# input3.net
KiCad netlist of a schematic drawn in Altium Designer
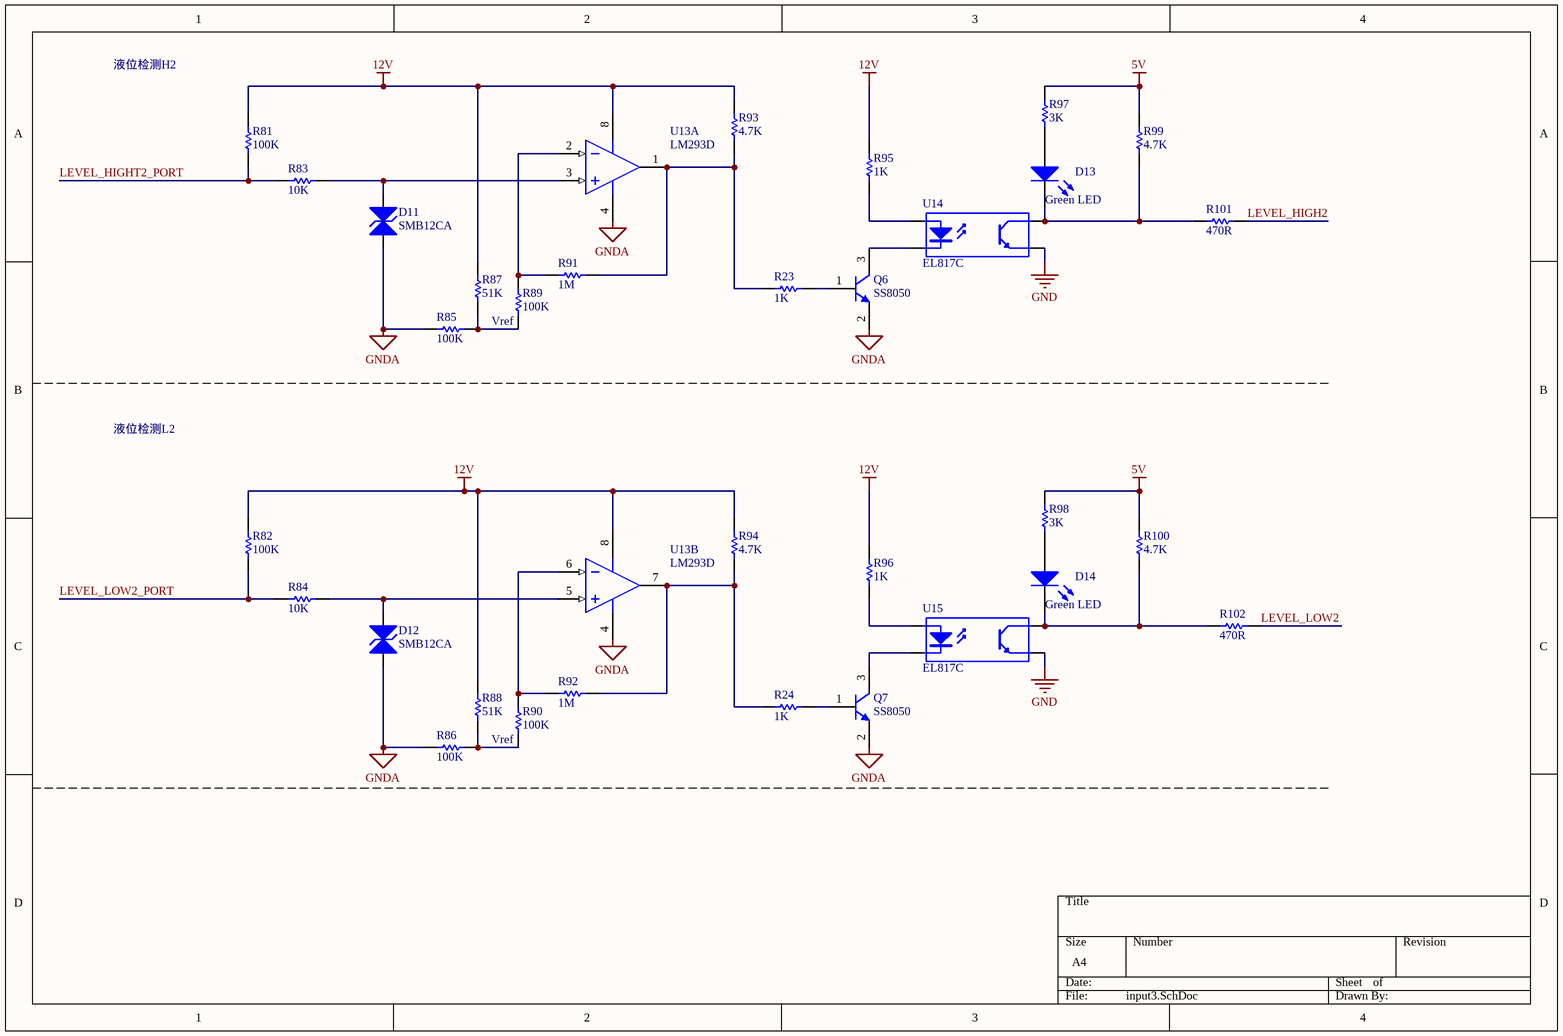
[diagram p0: input3.SchDoc]

(export (version "E")
  (design (tool "Eeschema 10.0.6"))
  (components
    (comp (ref "D11")
      (value "SMB12CA")
      (footprint "SMB")
      (description "Bi-dir TVS Diode")
      (fields (field (name "PUBLISHER") "Altium Limited"))
      (libsource (lib "UserLib") (part "Bi-dir TVS Diode"))
    )
    (comp (ref "D12")
      (value "SMB12CA")
      (footprint "SMB")
      (description "Bi-dir TVS Diode")
      (fields (field (name "PUBLISHER") "Altium Limited"))
      (libsource (lib "UserLib") (part "Bi-dir TVS Diode"))
    )
    (comp (ref "D13")
      (value "Green LED")
      (footprint "LED254A")
      (description "Green LED ,SIP, Dia =3mm")
      (fields (field (name "PUBLISHER") "Altium Limited"))
      (libsource (lib "Miscellaneous Devices") (part "LED1"))
    )
    (comp (ref "D14")
      (value "Green LED")
      (footprint "LED254A")
      (description "Green LED ,SIP, Dia =3mm")
      (fields (field (name "PUBLISHER") "Altium Limited"))
      (libsource (lib "Miscellaneous Devices") (part "LED1"))
    )
    (comp (ref "Q6")
      (value "SS8050")
      (footprint "SOT-23_N")
      (description "NPN BISS Transistor")
      (fields (field (name "PUBLISHER") "Altium Limited"))
      (libsource (lib "Philips Discrete BJT - Low Power") (part "PMMT491A"))
    )
    (comp (ref "Q7")
      (value "SS8050")
      (footprint "SOT-23_N")
      (description "NPN BISS Transistor")
      (fields (field (name "PUBLISHER") "Altium Limited"))
      (libsource (lib "Philips Discrete BJT - Low Power") (part "PMMT491A"))
    )
    (comp (ref "R23")
      (value "1K")
      (footprint "RESC2012M")
      (description "Resistor")
      (fields (field (name "PUBLISHER") "Altium Limited"))
      (libsource (lib "Miscellaneous Devices") (part "Res1"))
    )
    (comp (ref "R24")
      (value "1K")
      (footprint "RESC2012M")
      (description "Resistor")
      (fields (field (name "PUBLISHER") "Altium Limited"))
      (libsource (lib "Miscellaneous Devices") (part "Res1"))
    )
    (comp (ref "R81")
      (value "100K")
      (footprint "RESC2012M")
      (description "Resistor")
      (fields (field (name "PUBLISHER") "Altium Limited"))
      (libsource (lib "Miscellaneous Devices") (part "Res1"))
    )
    (comp (ref "R82")
      (value "100K")
      (footprint "RESC2012M")
      (description "Resistor")
      (fields (field (name "PUBLISHER") "Altium Limited"))
      (libsource (lib "Miscellaneous Devices") (part "Res1"))
    )
    (comp (ref "R83")
      (value "10K")
      (footprint "RESC2012M")
      (description "Resistor")
      (fields (field (name "PUBLISHER") "Altium Limited"))
      (libsource (lib "Miscellaneous Devices") (part "Res1"))
    )
    (comp (ref "R84")
      (value "10K")
      (footprint "RESC2012M")
      (description "Resistor")
      (fields (field (name "PUBLISHER") "Altium Limited"))
      (libsource (lib "Miscellaneous Devices") (part "Res1"))
    )
    (comp (ref "R85")
      (value "100K")
      (footprint "RESC2012M")
      (description "Resistor")
      (fields (field (name "PUBLISHER") "Altium Limited"))
      (libsource (lib "Miscellaneous Devices") (part "Res1"))
    )
    (comp (ref "R86")
      (value "100K")
      (footprint "RESC2012M")
      (description "Resistor")
      (fields (field (name "PUBLISHER") "Altium Limited"))
      (libsource (lib "Miscellaneous Devices") (part "Res1"))
    )
    (comp (ref "R87")
      (value "51K")
      (footprint "RESC2012M")
      (description "Resistor")
      (fields (field (name "PUBLISHER") "Altium Limited"))
      (libsource (lib "Miscellaneous Devices") (part "Res1"))
    )
    (comp (ref "R88")
      (value "51K")
      (footprint "RESC2012M")
      (description "Resistor")
      (fields (field (name "PUBLISHER") "Altium Limited"))
      (libsource (lib "Miscellaneous Devices") (part "Res1"))
    )
    (comp (ref "R89")
      (value "100K")
      (footprint "RESC2012M")
      (description "Resistor")
      (fields (field (name "PUBLISHER") "Altium Limited"))
      (libsource (lib "Miscellaneous Devices") (part "Res1"))
    )
    (comp (ref "R90")
      (value "100K")
      (footprint "RESC2012M")
      (description "Resistor")
      (fields (field (name "PUBLISHER") "Altium Limited"))
      (libsource (lib "Miscellaneous Devices") (part "Res1"))
    )
    (comp (ref "R91")
      (value "1M")
      (footprint "RESC2012M")
      (description "Resistor")
      (fields (field (name "PUBLISHER") "Altium Limited"))
      (libsource (lib "Miscellaneous Devices") (part "Res1"))
    )
    (comp (ref "R92")
      (value "1M")
      (footprint "RESC2012M")
      (description "Resistor")
      (fields (field (name "PUBLISHER") "Altium Limited"))
      (libsource (lib "Miscellaneous Devices") (part "Res1"))
    )
    (comp (ref "R93")
      (value "4.7K")
      (footprint "RESC2012M")
      (description "Resistor")
      (fields (field (name "PUBLISHER") "Altium Limited"))
      (libsource (lib "Miscellaneous Devices") (part "Res1"))
    )
    (comp (ref "R94")
      (value "4.7K")
      (footprint "RESC2012M")
      (description "Resistor")
      (fields (field (name "PUBLISHER") "Altium Limited"))
      (libsource (lib "Miscellaneous Devices") (part "Res1"))
    )
    (comp (ref "R95")
      (value "1K")
      (footprint "RESC2012M")
      (description "Resistor")
      (fields (field (name "PUBLISHER") "Altium Limited"))
      (libsource (lib "Miscellaneous Devices") (part "Res1"))
    )
    (comp (ref "R96")
      (value "1K")
      (footprint "RESC2012M")
      (description "Resistor")
      (fields (field (name "PUBLISHER") "Altium Limited"))
      (libsource (lib "Miscellaneous Devices") (part "Res1"))
    )
    (comp (ref "R97")
      (value "3K")
      (footprint "RESC2012M")
      (description "Resistor")
      (fields (field (name "PUBLISHER") "Altium Limited"))
      (libsource (lib "Miscellaneous Devices") (part "Res1"))
    )
    (comp (ref "R98")
      (value "3K")
      (footprint "RESC2012M")
      (description "Resistor")
      (fields (field (name "PUBLISHER") "Altium Limited"))
      (libsource (lib "Miscellaneous Devices") (part "Res1"))
    )
    (comp (ref "R99")
      (value "4.7K")
      (footprint "RESC2012M")
      (description "Resistor")
      (fields (field (name "PUBLISHER") "Altium Limited"))
      (libsource (lib "Miscellaneous Devices") (part "Res1"))
    )
    (comp (ref "R100")
      (value "4.7K")
      (footprint "RESC2012M")
      (description "Resistor")
      (fields (field (name "PUBLISHER") "Altium Limited"))
      (libsource (lib "Miscellaneous Devices") (part "Res1"))
    )
    (comp (ref "R101")
      (value "470R")
      (footprint "RESC2012M")
      (description "Resistor")
      (fields (field (name "PUBLISHER") "Altium Limited"))
      (libsource (lib "Miscellaneous Devices") (part "Res1"))
    )
    (comp (ref "R102")
      (value "470R")
      (footprint "RESC2012M")
      (description "Resistor")
      (fields (field (name "PUBLISHER") "Altium Limited"))
      (libsource (lib "Miscellaneous Devices") (part "Res1"))
    )
    (comp (ref "U13")
      (value "LM293D")
      (footprint "SO8_N")
      (description "Low-Power Dual Voltage Comparator")
      (fields (field (name "PUBLISHER") "Altium Limited"))
      (libsource (lib "ST Analog Comparator") (part "LM393AD"))
    )
    (comp (ref "U14")
      (value "EL817C")
      (footprint "SO-4LA")
      (description "4-Pin Phototransistor Optocoupler")
      (fields (field (name "PUBLISHER") "Altium Limited"))
      (libsource (lib "Miscellaneous Devices") (part "Optoisolator1"))
    )
    (comp (ref "U15")
      (value "EL817C")
      (footprint "SO-4LA")
      (description "4-Pin Phototransistor Optocoupler")
      (fields (field (name "PUBLISHER") "Altium Limited"))
      (libsource (lib "Miscellaneous Devices") (part "Optoisolator1"))
    )
  )
  (nets
    (net (code "1") (name "/LEVEL_HIGH2") (class "Default")
      (node (ref "R101") (pin "2") (pinfunction "2_2") (pintype "passive"))
    )
    (net (code "2") (name "/LEVEL_HIGHT2_PORT") (class "Default")
      (node (ref "R81") (pin "1") (pinfunction "1_1") (pintype "passive"))
      (node (ref "R83") (pin "2") (pinfunction "2_2") (pintype "passive"))
    )
    (net (code "3") (name "/LEVEL_LOW2") (class "Default")
      (node (ref "R102") (pin "2") (pinfunction "2_2") (pintype "passive"))
    )
    (net (code "4") (name "/LEVEL_LOW2_PORT") (class "Default")
      (node (ref "R82") (pin "1") (pinfunction "1_1") (pintype "passive"))
      (node (ref "R84") (pin "2") (pinfunction "2_2") (pintype "passive"))
    )
    (net (code "5") (name "5V") (class "Default")
      (node (ref "R100") (pin "2") (pinfunction "2_2") (pintype "passive"))
      (node (ref "R97") (pin "1") (pinfunction "1_1") (pintype "passive"))
      (node (ref "R98") (pin "1") (pinfunction "1_1") (pintype "passive"))
      (node (ref "R99") (pin "2") (pinfunction "2_2") (pintype "passive"))
    )
    (net (code "6") (name "12V") (class "Default")
      (node (ref "R81") (pin "2") (pinfunction "2_2") (pintype "passive"))
      (node (ref "R82") (pin "2") (pinfunction "2_2") (pintype "passive"))
      (node (ref "R87") (pin "2") (pinfunction "2_2") (pintype "passive"))
      (node (ref "R88") (pin "2") (pinfunction "2_2") (pintype "passive"))
      (node (ref "R93") (pin "1") (pinfunction "1_1") (pintype "passive"))
      (node (ref "R94") (pin "2") (pinfunction "2_2") (pintype "passive"))
      (node (ref "R95") (pin "1") (pinfunction "1_1") (pintype "passive"))
      (node (ref "R96") (pin "1") (pinfunction "1_1") (pintype "passive"))
      (node (ref "U13") (pin "8") (pinfunction "V+_8") (pintype "power_in"))
    )
    (net (code "7") (name "GND") (class "Default")
      (node (ref "U14") (pin "3") (pinfunction "E_3") (pintype "passive"))
      (node (ref "U15") (pin "3") (pinfunction "E_3") (pintype "passive"))
    )
    (net (code "8") (name "GNDA") (class "Default")
      (node (ref "D11") (pin "1") (pinfunction "A_1") (pintype "passive"))
      (node (ref "D12") (pin "1") (pinfunction "A_1") (pintype "passive"))
      (node (ref "Q6") (pin "2") (pinfunction "E_2") (pintype "passive"))
      (node (ref "Q7") (pin "2") (pinfunction "E_2") (pintype "passive"))
      (node (ref "R85") (pin "1") (pinfunction "1_1") (pintype "passive"))
      (node (ref "R86") (pin "1") (pinfunction "1_1") (pintype "passive"))
      (node (ref "U13") (pin "4") (pinfunction "V-_4") (pintype "power_in"))
    )
    (net (code "9") (name "Net-(D11-K)") (class "Default")
      (node (ref "D11") (pin "2") (pinfunction "K_2") (pintype "passive"))
      (node (ref "R83") (pin "1") (pinfunction "1_1") (pintype "passive"))
      (node (ref "U13") (pin "3") (pinfunction "IN+_3") (pintype "input"))
    )
    (net (code "10") (name "Net-(D12-K)") (class "Default")
      (node (ref "D12") (pin "2") (pinfunction "K_2") (pintype "passive"))
      (node (ref "R84") (pin "1") (pinfunction "1_1") (pintype "passive"))
      (node (ref "U13") (pin "5") (pinfunction "IN+_5") (pintype "input"))
    )
    (net (code "11") (name "Net-(D13-A)") (class "Default")
      (node (ref "D13") (pin "1") (pinfunction "A_1") (pintype "passive"))
      (node (ref "R97") (pin "2") (pinfunction "2_2") (pintype "passive"))
    )
    (net (code "12") (name "Net-(D13-K)") (class "Default")
      (node (ref "D13") (pin "2") (pinfunction "K_2") (pintype "passive"))
      (node (ref "R101") (pin "1") (pinfunction "1_1") (pintype "passive"))
      (node (ref "R99") (pin "1") (pinfunction "1_1") (pintype "passive"))
      (node (ref "U14") (pin "4") (pinfunction "C_4") (pintype "passive"))
    )
    (net (code "13") (name "Net-(D14-A)") (class "Default")
      (node (ref "D14") (pin "1") (pinfunction "A_1") (pintype "passive"))
      (node (ref "R98") (pin "2") (pinfunction "2_2") (pintype "passive"))
    )
    (net (code "14") (name "Net-(D14-K)") (class "Default")
      (node (ref "D14") (pin "2") (pinfunction "K_2") (pintype "passive"))
      (node (ref "R100") (pin "1") (pinfunction "1_1") (pintype "passive"))
      (node (ref "R102") (pin "1") (pinfunction "1_1") (pintype "passive"))
      (node (ref "U15") (pin "4") (pinfunction "C_4") (pintype "passive"))
    )
    (net (code "15") (name "Net-(Q6-B)") (class "Default")
      (node (ref "Q6") (pin "1") (pinfunction "B_1") (pintype "passive"))
      (node (ref "R23") (pin "2") (pinfunction "2_2") (pintype "passive"))
    )
    (net (code "16") (name "Net-(Q6-C)") (class "Default")
      (node (ref "Q6") (pin "3") (pinfunction "C_3") (pintype "passive"))
      (node (ref "U14") (pin "2") (pinfunction "K_2") (pintype "passive"))
    )
    (net (code "17") (name "Net-(Q7-B)") (class "Default")
      (node (ref "Q7") (pin "1") (pinfunction "B_1") (pintype "passive"))
      (node (ref "R24") (pin "2") (pinfunction "2_2") (pintype "passive"))
    )
    (net (code "18") (name "Net-(Q7-C)") (class "Default")
      (node (ref "Q7") (pin "3") (pinfunction "C_3") (pintype "passive"))
      (node (ref "U15") (pin "2") (pinfunction "K_2") (pintype "passive"))
    )
    (net (code "19") (name "Net-(R85-Pad2)") (class "Default")
      (node (ref "R85") (pin "2") (pinfunction "2_2") (pintype "passive"))
      (node (ref "R87") (pin "1") (pinfunction "1_1") (pintype "passive"))
      (node (ref "R89") (pin "2") (pinfunction "2_2") (pintype "passive"))
    )
    (net (code "20") (name "Net-(R86-Pad2)") (class "Default")
      (node (ref "R86") (pin "2") (pinfunction "2_2") (pintype "passive"))
      (node (ref "R88") (pin "1") (pinfunction "1_1") (pintype "passive"))
      (node (ref "R90") (pin "1") (pinfunction "1_1") (pintype "passive"))
    )
    (net (code "21") (name "Net-(U13A-IN-)") (class "Default")
      (node (ref "R89") (pin "1") (pinfunction "1_1") (pintype "passive"))
      (node (ref "R91") (pin "1") (pinfunction "1_1") (pintype "passive"))
      (node (ref "U13") (pin "2") (pinfunction "IN-_2") (pintype "input"))
    )
    (net (code "22") (name "Net-(U13A-OUT)") (class "Default")
      (node (ref "R23") (pin "1") (pinfunction "1_1") (pintype "passive"))
      (node (ref "R91") (pin "2") (pinfunction "2_2") (pintype "passive"))
      (node (ref "R93") (pin "2") (pinfunction "2_2") (pintype "passive"))
      (node (ref "U13") (pin "1") (pinfunction "OUT_1") (pintype "open_collector"))
    )
    (net (code "23") (name "Net-(U13B-IN-)") (class "Default")
      (node (ref "R90") (pin "2") (pinfunction "2_2") (pintype "passive"))
      (node (ref "R92") (pin "1") (pinfunction "1_1") (pintype "passive"))
      (node (ref "U13") (pin "6") (pinfunction "IN-_6") (pintype "input"))
    )
    (net (code "24") (name "Net-(U13B-OUT)") (class "Default")
      (node (ref "R24") (pin "1") (pinfunction "1_1") (pintype "passive"))
      (node (ref "R92") (pin "2") (pinfunction "2_2") (pintype "passive"))
      (node (ref "R94") (pin "1") (pinfunction "1_1") (pintype "passive"))
      (node (ref "U13") (pin "7") (pinfunction "OUT_7") (pintype "open_collector"))
    )
    (net (code "25") (name "Net-(U14-A)") (class "Default")
      (node (ref "R95") (pin "2") (pinfunction "2_2") (pintype "passive"))
      (node (ref "U14") (pin "1") (pinfunction "A_1") (pintype "passive"))
    )
    (net (code "26") (name "Net-(U15-A)") (class "Default")
      (node (ref "R96") (pin "2") (pinfunction "2_2") (pintype "passive"))
      (node (ref "U15") (pin "1") (pinfunction "A_1") (pintype "passive"))
    )
  )
)
